# ESP32_adapter_revB.net
KiCad netlist of a schematic drawn in EAGLE
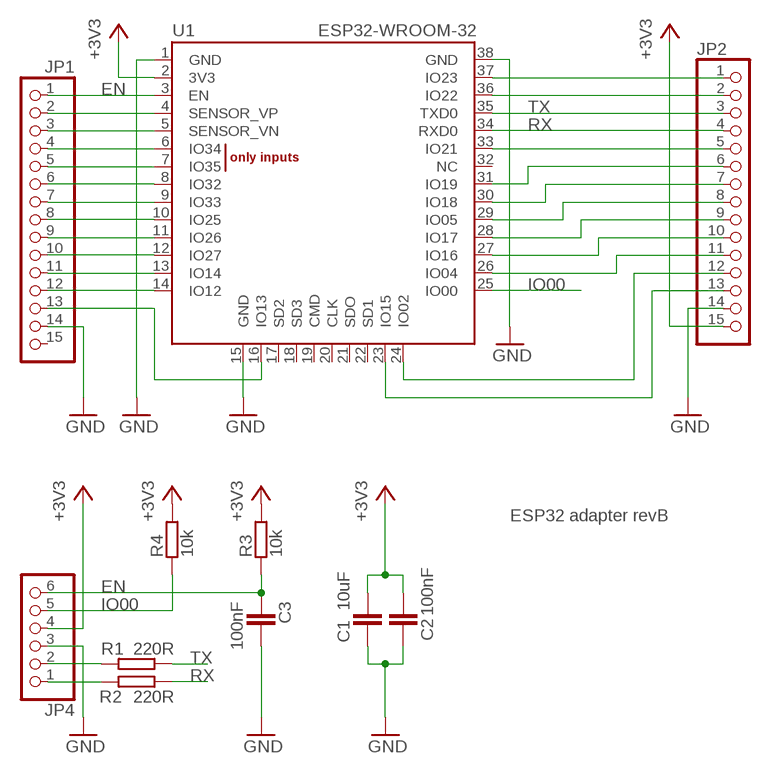
[diagram p0: schematic, sheet 1]

(export (version "E")
  (design (tool "Eeschema 10.0.6"))
  (components
    (comp (ref "C1")
      (value "10uF")
      (footprint "eagle-import:C0805")
      (libsource (lib "eagle-import") (part "C-CERAMIC'SMD'"))
    )
    (comp (ref "C2")
      (value "100nF")
      (footprint "eagle-import:C0805")
      (libsource (lib "eagle-import") (part "C-CERAMIC'SMD'"))
    )
    (comp (ref "C3")
      (value "100nF")
      (footprint "eagle-import:C0805")
      (libsource (lib "eagle-import") (part "C-CERAMIC'SMD'"))
    )
    (comp (ref "JP1")
      (value "PINHD-1X15")
      (footprint "eagle-import:1X15")
      (libsource (lib "eagle-import") (part "PINHD-1X15"))
    )
    (comp (ref "JP2")
      (value "PINHD-1X15")
      (footprint "eagle-import:1X15")
      (libsource (lib "eagle-import") (part "PINHD-1X15"))
    )
    (comp (ref "JP4")
      (value "PINHD-1X6")
      (footprint "eagle-import:1X06")
      (libsource (lib "eagle-import") (part "PINHD-1X6"))
    )
    (comp (ref "R1")
      (value "220R")
      (footprint "eagle-import:R0805")
      (libsource (lib "eagle-import") (part "R'2'"))
    )
    (comp (ref "R2")
      (value "220R")
      (footprint "eagle-import:R0805")
      (libsource (lib "eagle-import") (part "R'2'"))
    )
    (comp (ref "R3")
      (value "10k")
      (footprint "eagle-import:R0805")
      (libsource (lib "eagle-import") (part "R'2'"))
    )
    (comp (ref "R4")
      (value "10k")
      (footprint "eagle-import:R0805")
      (libsource (lib "eagle-import") (part "R'2'"))
    )
    (comp (ref "U1")
      (value "ESP-WROOM-32")
      (footprint "eagle-import:ESP-WROOM-32")
      (libsource (lib "eagle-import") (part "ESP-WROOM-32"))
    )
  )
  (nets
    (net (code "1") (name "+3V3") (class "Default")
      (node (ref "C1") (pin "2") (pinfunction "P$2_2") (pintype "bidirectional"))
      (node (ref "C2") (pin "2") (pinfunction "P$2_2") (pintype "bidirectional"))
      (node (ref "JP2") (pin "15") (pinfunction "15_15") (pintype "passive"))
      (node (ref "JP4") (pin "4") (pinfunction "4_4") (pintype "passive"))
      (node (ref "R3") (pin "2") (pinfunction "P$2_2") (pintype "bidirectional"))
      (node (ref "R4") (pin "2") (pinfunction "P$2_2") (pintype "bidirectional"))
      (node (ref "U1") (pin "2") (pinfunction "3V3_2") (pintype "bidirectional"))
    )
    (net (code "2") (name "/EN") (class "Default")
      (node (ref "C3") (pin "1") (pinfunction "P$1_1") (pintype "bidirectional"))
      (node (ref "JP1") (pin "1") (pinfunction "1_1") (pintype "passive"))
      (node (ref "JP4") (pin "6") (pinfunction "6_6") (pintype "passive"))
      (node (ref "R3") (pin "1") (pinfunction "P$1_1") (pintype "bidirectional"))
      (node (ref "U1") (pin "3") (pinfunction "EN_3") (pintype "bidirectional"))
    )
    (net (code "3") (name "/IO00") (class "Default")
      (node (ref "JP4") (pin "5") (pinfunction "5_5") (pintype "passive"))
      (node (ref "R4") (pin "1") (pinfunction "P$1_1") (pintype "bidirectional"))
      (node (ref "U1") (pin "25") (pinfunction "IO00_25") (pintype "bidirectional"))
    )
    (net (code "4") (name "/RX") (class "Default")
      (node (ref "JP2") (pin "4") (pinfunction "4_4") (pintype "passive"))
      (node (ref "R2") (pin "2") (pinfunction "P$2_2") (pintype "bidirectional"))
      (node (ref "U1") (pin "34") (pinfunction "RXD0_34") (pintype "bidirectional"))
    )
    (net (code "5") (name "/TX") (class "Default")
      (node (ref "JP2") (pin "3") (pinfunction "3_3") (pintype "passive"))
      (node (ref "R1") (pin "2") (pinfunction "P$2_2") (pintype "bidirectional"))
      (node (ref "U1") (pin "35") (pinfunction "TXD0_35") (pintype "bidirectional"))
    )
    (net (code "6") (name "GND") (class "Default")
      (node (ref "C1") (pin "1") (pinfunction "P$1_1") (pintype "bidirectional"))
      (node (ref "C2") (pin "1") (pinfunction "P$1_1") (pintype "bidirectional"))
      (node (ref "C3") (pin "2") (pinfunction "P$2_2") (pintype "bidirectional"))
      (node (ref "JP1") (pin "14") (pinfunction "14_14") (pintype "passive"))
      (node (ref "JP2") (pin "14") (pinfunction "14_14") (pintype "passive"))
      (node (ref "JP4") (pin "3") (pinfunction "3_3") (pintype "passive"))
      (node (ref "U1") (pin "1") (pinfunction "GND_1") (pintype "bidirectional"))
      (node (ref "U1") (pin "15") (pinfunction "GND_15") (pintype "bidirectional"))
      (node (ref "U1") (pin "38") (pinfunction "GND_38") (pintype "bidirectional"))
    )
    (net (code "7") (name "Net-(R1-P$1)") (class "Default")
      (node (ref "JP4") (pin "2") (pinfunction "2_2") (pintype "passive"))
      (node (ref "R1") (pin "1") (pinfunction "P$1_1") (pintype "bidirectional"))
    )
    (net (code "8") (name "Net-(R2-P$1)") (class "Default")
      (node (ref "JP4") (pin "1") (pinfunction "1_1") (pintype "passive"))
      (node (ref "R2") (pin "1") (pinfunction "P$1_1") (pintype "bidirectional"))
    )
    (net (code "9") (name "Net-(U1-IO02)") (class "Default")
      (node (ref "JP2") (pin "12") (pinfunction "12_12") (pintype "passive"))
      (node (ref "U1") (pin "24") (pinfunction "IO02_24") (pintype "bidirectional"))
    )
    (net (code "10") (name "Net-(U1-IO04)") (class "Default")
      (node (ref "JP2") (pin "11") (pinfunction "11_11") (pintype "passive"))
      (node (ref "U1") (pin "26") (pinfunction "IO04_26") (pintype "bidirectional"))
    )
    (net (code "11") (name "Net-(U1-IO05)") (class "Default")
      (node (ref "JP2") (pin "8") (pinfunction "8_8") (pintype "passive"))
      (node (ref "U1") (pin "29") (pinfunction "IO05_29") (pintype "bidirectional"))
    )
    (net (code "12") (name "Net-(U1-IO12)") (class "Default")
      (node (ref "JP1") (pin "12") (pinfunction "12_12") (pintype "passive"))
      (node (ref "U1") (pin "14") (pinfunction "IO12_14") (pintype "bidirectional"))
    )
    (net (code "13") (name "Net-(U1-IO13)") (class "Default")
      (node (ref "JP1") (pin "13") (pinfunction "13_13") (pintype "passive"))
      (node (ref "U1") (pin "16") (pinfunction "IO13_16") (pintype "bidirectional"))
    )
    (net (code "14") (name "Net-(U1-IO14)") (class "Default")
      (node (ref "JP1") (pin "11") (pinfunction "11_11") (pintype "passive"))
      (node (ref "U1") (pin "13") (pinfunction "IO14_13") (pintype "bidirectional"))
    )
    (net (code "15") (name "Net-(U1-IO15)") (class "Default")
      (node (ref "JP2") (pin "13") (pinfunction "13_13") (pintype "passive"))
      (node (ref "U1") (pin "23") (pinfunction "IO15_23") (pintype "bidirectional"))
    )
    (net (code "16") (name "Net-(U1-IO16)") (class "Default")
      (node (ref "JP2") (pin "10") (pinfunction "10_10") (pintype "passive"))
      (node (ref "U1") (pin "27") (pinfunction "IO16_27") (pintype "bidirectional"))
    )
    (net (code "17") (name "Net-(U1-IO17)") (class "Default")
      (node (ref "JP2") (pin "9") (pinfunction "9_9") (pintype "passive"))
      (node (ref "U1") (pin "28") (pinfunction "IO17_28") (pintype "bidirectional"))
    )
    (net (code "18") (name "Net-(U1-IO18)") (class "Default")
      (node (ref "JP2") (pin "7") (pinfunction "7_7") (pintype "passive"))
      (node (ref "U1") (pin "30") (pinfunction "IO18_30") (pintype "bidirectional"))
    )
    (net (code "19") (name "Net-(U1-IO19)") (class "Default")
      (node (ref "JP2") (pin "6") (pinfunction "6_6") (pintype "passive"))
      (node (ref "U1") (pin "31") (pinfunction "IO19_31") (pintype "bidirectional"))
    )
    (net (code "20") (name "Net-(U1-IO21)") (class "Default")
      (node (ref "JP2") (pin "5") (pinfunction "5_5") (pintype "passive"))
      (node (ref "U1") (pin "33") (pinfunction "IO21_33") (pintype "bidirectional"))
    )
    (net (code "21") (name "Net-(U1-IO22)") (class "Default")
      (node (ref "JP2") (pin "2") (pinfunction "2_2") (pintype "passive"))
      (node (ref "U1") (pin "36") (pinfunction "IO22_36") (pintype "bidirectional"))
    )
    (net (code "22") (name "Net-(U1-IO23)") (class "Default")
      (node (ref "JP2") (pin "1") (pinfunction "1_1") (pintype "passive"))
      (node (ref "U1") (pin "37") (pinfunction "IO23_37") (pintype "bidirectional"))
    )
    (net (code "23") (name "Net-(U1-IO25)") (class "Default")
      (node (ref "JP1") (pin "8") (pinfunction "8_8") (pintype "passive"))
      (node (ref "U1") (pin "10") (pinfunction "IO25_10") (pintype "bidirectional"))
    )
    (net (code "24") (name "Net-(U1-IO26)") (class "Default")
      (node (ref "JP1") (pin "9") (pinfunction "9_9") (pintype "passive"))
      (node (ref "U1") (pin "11") (pinfunction "IO26_11") (pintype "bidirectional"))
    )
    (net (code "25") (name "Net-(U1-IO27)") (class "Default")
      (node (ref "JP1") (pin "10") (pinfunction "10_10") (pintype "passive"))
      (node (ref "U1") (pin "12") (pinfunction "IO27_12") (pintype "bidirectional"))
    )
    (net (code "26") (name "Net-(U1-IO32)") (class "Default")
      (node (ref "JP1") (pin "6") (pinfunction "6_6") (pintype "passive"))
      (node (ref "U1") (pin "8") (pinfunction "IO32_8") (pintype "bidirectional"))
    )
    (net (code "27") (name "Net-(U1-IO33)") (class "Default")
      (node (ref "JP1") (pin "7") (pinfunction "7_7") (pintype "passive"))
      (node (ref "U1") (pin "9") (pinfunction "IO33_9") (pintype "bidirectional"))
    )
    (net (code "28") (name "Net-(U1-IO34)") (class "Default")
      (node (ref "JP1") (pin "4") (pinfunction "4_4") (pintype "passive"))
      (node (ref "U1") (pin "6") (pinfunction "IO34_6") (pintype "input"))
    )
    (net (code "29") (name "Net-(U1-IO35)") (class "Default")
      (node (ref "JP1") (pin "5") (pinfunction "5_5") (pintype "passive"))
      (node (ref "U1") (pin "7") (pinfunction "IO35_7") (pintype "input"))
    )
    (net (code "30") (name "Net-(U1-SENSOR_VN)") (class "Default")
      (node (ref "JP1") (pin "3") (pinfunction "3_3") (pintype "passive"))
      (node (ref "U1") (pin "5") (pinfunction "SENSOR_VN_5") (pintype "input"))
    )
    (net (code "31") (name "Net-(U1-SENSOR_VP)") (class "Default")
      (node (ref "JP1") (pin "2") (pinfunction "2_2") (pintype "passive"))
      (node (ref "U1") (pin "4") (pinfunction "SENSOR_VP_4") (pintype "input"))
    )
    (net (code "32") (name "unconnected-(JP1-Pad15)") (class "Default")
      (node (ref "JP1") (pin "15") (pinfunction "15_15") (pintype "passive"))
    )
    (net (code "33") (name "unconnected-(U1-CLK-Pad20)") (class "Default")
      (node (ref "U1") (pin "20") (pinfunction "CLK_20") (pintype "bidirectional"))
    )
    (net (code "34") (name "unconnected-(U1-CMD-Pad19)") (class "Default")
      (node (ref "U1") (pin "19") (pinfunction "CMD_19") (pintype "bidirectional"))
    )
    (net (code "35") (name "unconnected-(U1-NC-Pad32)") (class "Default")
      (node (ref "U1") (pin "32") (pinfunction "NC_32") (pintype "bidirectional"))
    )
    (net (code "36") (name "unconnected-(U1-SD1-Pad22)") (class "Default")
      (node (ref "U1") (pin "22") (pinfunction "SD1_22") (pintype "bidirectional"))
    )
    (net (code "37") (name "unconnected-(U1-SD2-Pad17)") (class "Default")
      (node (ref "U1") (pin "17") (pinfunction "SD2_17") (pintype "bidirectional"))
    )
    (net (code "38") (name "unconnected-(U1-SD3-Pad18)") (class "Default")
      (node (ref "U1") (pin "18") (pinfunction "SD3_18") (pintype "bidirectional"))
    )
    (net (code "39") (name "unconnected-(U1-SDO-Pad21)") (class "Default")
      (node (ref "U1") (pin "21") (pinfunction "SDO_21") (pintype "bidirectional"))
    )
  )
)
